# BackPage.net
KiCad netlist of a schematic drawn in Altium Designer
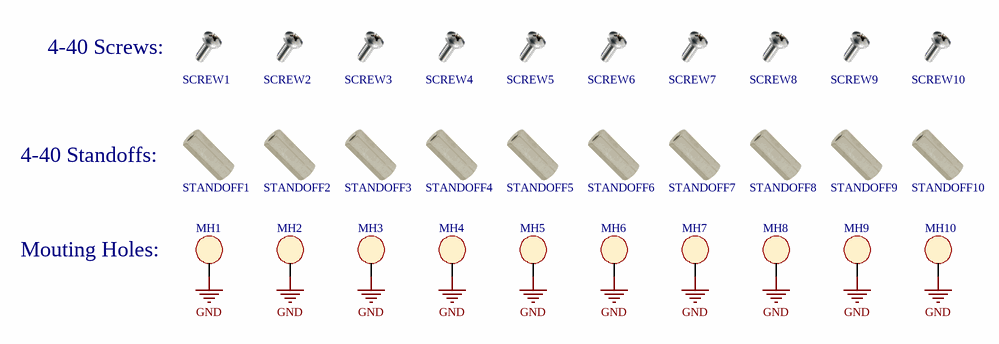
[diagram p0: BackPage.SchDoc]

(export (version "E")
  (design (tool "Eeschema 10.0.6"))
  (components
    (comp (ref "MH1")
      (value "MOUNT_HOLE")
      (footprint "AMDC:MOUNTING_HOLE")
      (description "MOUNTING HOLE")
      (libsource (lib "AMDC") (part "MOUNT_HOLE"))
    )
    (comp (ref "MH2")
      (value "MOUNT_HOLE")
      (footprint "AMDC:MOUNTING_HOLE")
      (description "MOUNTING HOLE")
      (libsource (lib "AMDC") (part "MOUNT_HOLE"))
    )
    (comp (ref "MH3")
      (value "MOUNT_HOLE")
      (footprint "AMDC:MOUNTING_HOLE")
      (description "MOUNTING HOLE")
      (libsource (lib "AMDC") (part "MOUNT_HOLE"))
    )
    (comp (ref "MH4")
      (value "MOUNT_HOLE")
      (footprint "AMDC:MOUNTING_HOLE")
      (description "MOUNTING HOLE")
      (libsource (lib "AMDC") (part "MOUNT_HOLE"))
    )
    (comp (ref "MH5")
      (value "MOUNT_HOLE")
      (footprint "AMDC:MOUNTING_HOLE")
      (description "MOUNTING HOLE")
      (libsource (lib "AMDC") (part "MOUNT_HOLE"))
    )
    (comp (ref "MH6")
      (value "MOUNT_HOLE")
      (footprint "AMDC:MOUNTING_HOLE")
      (description "MOUNTING HOLE")
      (libsource (lib "AMDC") (part "MOUNT_HOLE"))
    )
    (comp (ref "MH7")
      (value "MOUNT_HOLE")
      (footprint "AMDC:MOUNTING_HOLE")
      (description "MOUNTING HOLE")
      (libsource (lib "AMDC") (part "MOUNT_HOLE"))
    )
    (comp (ref "MH8")
      (value "MOUNT_HOLE")
      (footprint "AMDC:MOUNTING_HOLE")
      (description "MOUNTING HOLE")
      (libsource (lib "AMDC") (part "MOUNT_HOLE"))
    )
    (comp (ref "MH9")
      (value "MOUNT_HOLE")
      (footprint "AMDC:MOUNTING_HOLE")
      (description "MOUNTING HOLE")
      (libsource (lib "AMDC") (part "MOUNT_HOLE"))
    )
    (comp (ref "MH10")
      (value "MOUNT_HOLE")
      (footprint "AMDC:MOUNTING_HOLE")
      (description "MOUNTING HOLE")
      (libsource (lib "AMDC") (part "MOUNT_HOLE"))
    )
    (comp (ref "SCREW1") (value "Screw-4-40") (libsource (lib "AMDC") (part "Screw-4-40")))
    (comp (ref "SCREW2") (value "Screw-4-40") (libsource (lib "AMDC") (part "Screw-4-40")))
    (comp (ref "SCREW3") (value "Screw-4-40") (libsource (lib "AMDC") (part "Screw-4-40")))
    (comp (ref "SCREW4") (value "Screw-4-40") (libsource (lib "AMDC") (part "Screw-4-40")))
    (comp (ref "SCREW5") (value "Screw-4-40") (libsource (lib "AMDC") (part "Screw-4-40")))
    (comp (ref "SCREW6") (value "Screw-4-40") (libsource (lib "AMDC") (part "Screw-4-40")))
    (comp (ref "SCREW7") (value "Screw-4-40") (libsource (lib "AMDC") (part "Screw-4-40")))
    (comp (ref "SCREW8") (value "Screw-4-40") (libsource (lib "AMDC") (part "Screw-4-40")))
    (comp (ref "SCREW9") (value "Screw-4-40") (libsource (lib "AMDC") (part "Screw-4-40")))
    (comp (ref "SCREW10") (value "Screw-4-40") (libsource (lib "AMDC") (part "Screw-4-40")))
    (comp (ref "STANDOFF1") (value "Standoff-4-40") (libsource (lib "AMDC") (part "Standoff-4-40")))
    (comp (ref "STANDOFF2") (value "Standoff-4-40") (libsource (lib "AMDC") (part "Standoff-4-40")))
    (comp (ref "STANDOFF3") (value "Standoff-4-40") (libsource (lib "AMDC") (part "Standoff-4-40")))
    (comp (ref "STANDOFF4") (value "Standoff-4-40") (libsource (lib "AMDC") (part "Standoff-4-40")))
    (comp (ref "STANDOFF5") (value "Standoff-4-40") (libsource (lib "AMDC") (part "Standoff-4-40")))
    (comp (ref "STANDOFF6") (value "Standoff-4-40") (libsource (lib "AMDC") (part "Standoff-4-40")))
    (comp (ref "STANDOFF7") (value "Standoff-4-40") (libsource (lib "AMDC") (part "Standoff-4-40")))
    (comp (ref "STANDOFF8") (value "Standoff-4-40") (libsource (lib "AMDC") (part "Standoff-4-40")))
    (comp (ref "STANDOFF9") (value "Standoff-4-40") (libsource (lib "AMDC") (part "Standoff-4-40")))
    (comp (ref "STANDOFF10") (value "Standoff-4-40") (libsource (lib "AMDC") (part "Standoff-4-40")))
  )
  (nets
    (net (code "1") (name "GND") (class "Default")
      (node (ref "MH1") (pin "1") (pinfunction "1_1") (pintype "passive"))
      (node (ref "MH10") (pin "1") (pinfunction "1_1") (pintype "passive"))
      (node (ref "MH2") (pin "1") (pinfunction "1_1") (pintype "passive"))
      (node (ref "MH3") (pin "1") (pinfunction "1_1") (pintype "passive"))
      (node (ref "MH4") (pin "1") (pinfunction "1_1") (pintype "passive"))
      (node (ref "MH5") (pin "1") (pinfunction "1_1") (pintype "passive"))
      (node (ref "MH6") (pin "1") (pinfunction "1_1") (pintype "passive"))
      (node (ref "MH7") (pin "1") (pinfunction "1_1") (pintype "passive"))
      (node (ref "MH8") (pin "1") (pinfunction "1_1") (pintype "passive"))
      (node (ref "MH9") (pin "1") (pinfunction "1_1") (pintype "passive"))
    )
  )
)
